# BEP21.net
KiCad netlist of a schematic drawn in EAGLE
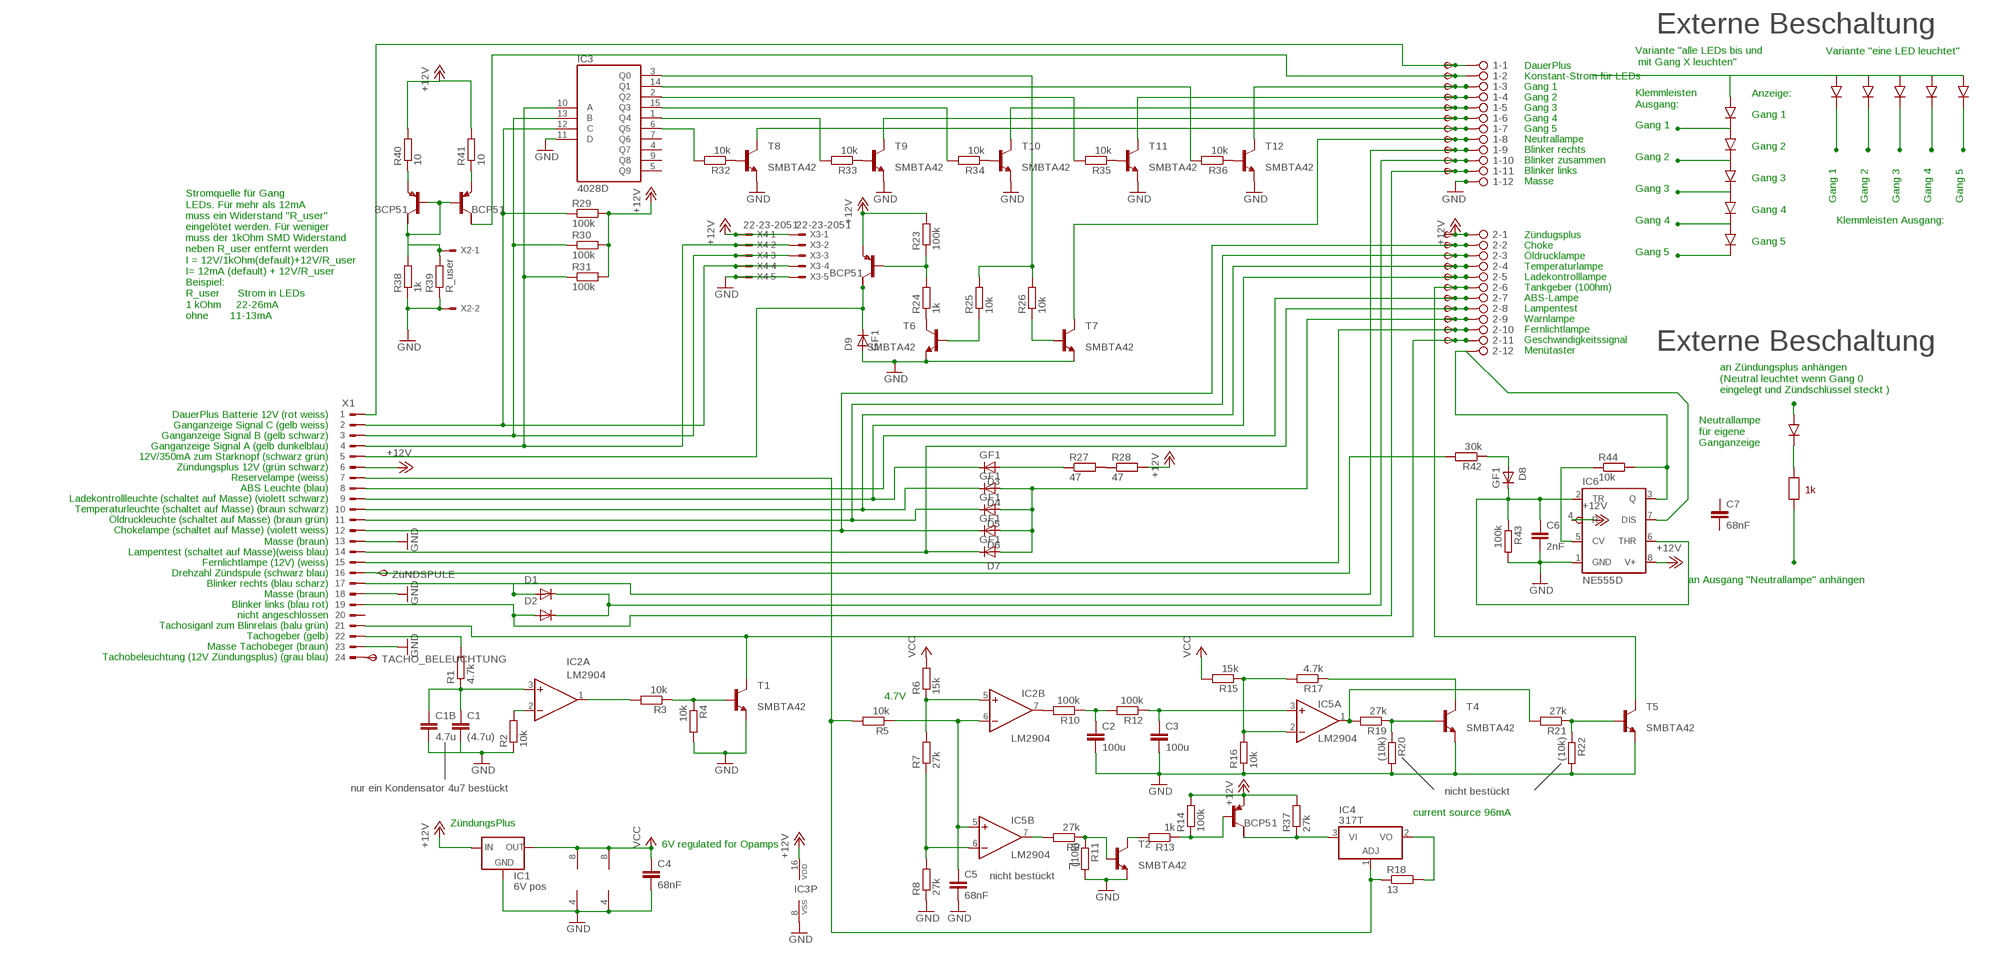
[diagram p0: schematic, sheet 1]

(export (version "E")
  (design (tool "Eeschema 10.0.6"))
  (components
    (comp (ref "1")
      (value "2081-1132")
      (footprint "eagle-import:12-PIN")
      (libsource (lib "eagle-import") (part "2081-1132"))
    )
    (comp (ref "2")
      (value "2081-1132")
      (footprint "eagle-import:12-PIN")
      (libsource (lib "eagle-import") (part "2081-1132"))
    )
    (comp (ref "C1")
      (value "(4.7u)")
      (footprint "eagle-import:C1206")
      (libsource (lib "eagle-import") (part "C-EUC1206"))
    )
    (comp (ref "C1B")
      (value "4.7u")
      (footprint "eagle-import:C0805K")
      (libsource (lib "eagle-import") (part "C-EUC0805K"))
    )
    (comp (ref "C2")
      (value "100u")
      (footprint "eagle-import:C1206K")
      (libsource (lib "eagle-import") (part "C-EUC1206K"))
    )
    (comp (ref "C3")
      (value "100u")
      (footprint "eagle-import:C1206K")
      (libsource (lib "eagle-import") (part "C-EUC1206K"))
    )
    (comp (ref "C4")
      (value "68nF")
      (footprint "eagle-import:C1206K")
      (libsource (lib "eagle-import") (part "C-EUC1206K"))
    )
    (comp (ref "C5")
      (value "68nF")
      (footprint "eagle-import:C1206K")
      (libsource (lib "eagle-import") (part "C-EUC1206K"))
    )
    (comp (ref "C6")
      (value "2nF")
      (footprint "eagle-import:C1206K")
      (libsource (lib "eagle-import") (part "C-EUC1206K"))
    )
    (comp (ref "C7")
      (value "68nF")
      (footprint "eagle-import:C1206K")
      (libsource (lib "eagle-import") (part "C-EUC1206K"))
    )
    (comp (ref "D1")
      (value "GF1")
      (footprint "eagle-import:SMA-DO214AC")
      (libsource (lib "eagle-import") (part "GF1"))
    )
    (comp (ref "D2")
      (value "GF1")
      (footprint "eagle-import:SMA-DO214AC")
      (libsource (lib "eagle-import") (part "GF1"))
    )
    (comp (ref "D3")
      (value "GF1")
      (footprint "eagle-import:SMA-DO214AC")
      (libsource (lib "eagle-import") (part "GF1"))
    )
    (comp (ref "D4")
      (value "GF1")
      (footprint "eagle-import:SMA-DO214AC")
      (libsource (lib "eagle-import") (part "GF1"))
    )
    (comp (ref "D5")
      (value "GF1")
      (footprint "eagle-import:SMA-DO214AC")
      (libsource (lib "eagle-import") (part "GF1"))
    )
    (comp (ref "D6")
      (value "GF1")
      (footprint "eagle-import:SMA-DO214AC")
      (libsource (lib "eagle-import") (part "GF1"))
    )
    (comp (ref "D7")
      (value "GF1")
      (footprint "eagle-import:SMA-DO214AC")
      (libsource (lib "eagle-import") (part "GF1"))
    )
    (comp (ref "D8")
      (value "GF1")
      (footprint "eagle-import:SMA-DO214AC")
      (libsource (lib "eagle-import") (part "GF1"))
    )
    (comp (ref "D9")
      (value "GF1")
      (footprint "eagle-import:SMA-DO214AC")
      (libsource (lib "eagle-import") (part "GF1"))
    )
    (comp (ref "IC1")
      (value "6V pos")
      (footprint "eagle-import:78LXX")
      (libsource (lib "eagle-import") (part "78LXX"))
    )
    (comp (ref "IC2")
      (value "LM2904")
      (footprint "eagle-import:SO08")
      (fields (field (name "IC") "LM2904"))
      (libsource (lib "eagle-import") (part "LM358D"))
    )
    (comp (ref "IC3")
      (value "4028D")
      (footprint "eagle-import:SO16")
      (libsource (lib "eagle-import") (part "4028D"))
    )
    (comp (ref "IC4")
      (value "317T")
      (footprint "eagle-import:TO220H")
      (libsource (lib "eagle-import") (part "317T"))
    )
    (comp (ref "IC5")
      (value "LM2904")
      (footprint "eagle-import:SO08")
      (libsource (lib "eagle-import") (part "linear_BMW_LM358D"))
    )
    (comp (ref "IC6")
      (value "NE555D")
      (footprint "eagle-import:SO08")
      (libsource (lib "eagle-import") (part "555DNE"))
    )
    (comp (ref "R1")
      (value "4.7k")
      (footprint "eagle-import:R0805")
      (libsource (lib "eagle-import") (part "R-EU_R0805"))
    )
    (comp (ref "R2")
      (value "10k")
      (footprint "eagle-import:R0805")
      (libsource (lib "eagle-import") (part "R-EU_R0805"))
    )
    (comp (ref "R3")
      (value "10k")
      (footprint "eagle-import:R0805")
      (libsource (lib "eagle-import") (part "R-EU_R0805"))
    )
    (comp (ref "R4")
      (value "10k")
      (footprint "eagle-import:R0805")
      (libsource (lib "eagle-import") (part "R-EU_R0805"))
    )
    (comp (ref "R5")
      (value "10k")
      (footprint "eagle-import:R0805")
      (libsource (lib "eagle-import") (part "R-EU_R0805"))
    )
    (comp (ref "R6")
      (value "15k")
      (footprint "eagle-import:R0805")
      (libsource (lib "eagle-import") (part "R-EU_R0805"))
    )
    (comp (ref "R7")
      (value "27k")
      (footprint "eagle-import:R0805")
      (libsource (lib "eagle-import") (part "R-EU_R0805"))
    )
    (comp (ref "R8")
      (value "27k")
      (footprint "eagle-import:R0805")
      (libsource (lib "eagle-import") (part "R-EU_R0805"))
    )
    (comp (ref "R9")
      (value "27k")
      (footprint "eagle-import:R0805")
      (libsource (lib "eagle-import") (part "R-EU_R0805"))
    )
    (comp (ref "R10")
      (value "100k")
      (footprint "eagle-import:R0805")
      (libsource (lib "eagle-import") (part "R-EU_R0805"))
    )
    (comp (ref "R11")
      (value "(10k)")
      (footprint "eagle-import:R0805")
      (libsource (lib "eagle-import") (part "R-EU_R0805"))
    )
    (comp (ref "R12")
      (value "100k")
      (footprint "eagle-import:R0805")
      (libsource (lib "eagle-import") (part "R-EU_R0805"))
    )
    (comp (ref "R13")
      (value "1k")
      (footprint "eagle-import:R0805")
      (libsource (lib "eagle-import") (part "R-EU_R0805"))
    )
    (comp (ref "R14")
      (value "100k")
      (footprint "eagle-import:R0805")
      (libsource (lib "eagle-import") (part "R-EU_R0805"))
    )
    (comp (ref "R15")
      (value "15k")
      (footprint "eagle-import:R0805")
      (libsource (lib "eagle-import") (part "R-EU_R0805"))
    )
    (comp (ref "R16")
      (value "10k")
      (footprint "eagle-import:R0805")
      (libsource (lib "eagle-import") (part "R-EU_R0805"))
    )
    (comp (ref "R17")
      (value "4.7k")
      (footprint "eagle-import:R0805")
      (libsource (lib "eagle-import") (part "R-EU_R0805"))
    )
    (comp (ref "R18")
      (value "13")
      (footprint "eagle-import:0207_10")
      (libsource (lib "eagle-import") (part "R-EU_0207/10"))
    )
    (comp (ref "R19")
      (value "27k")
      (footprint "eagle-import:R0805")
      (libsource (lib "eagle-import") (part "R-EU_R0805"))
    )
    (comp (ref "R20")
      (value "(10k)")
      (footprint "eagle-import:R0805")
      (libsource (lib "eagle-import") (part "R-EU_R0805"))
    )
    (comp (ref "R21")
      (value "27k")
      (footprint "eagle-import:R0805")
      (libsource (lib "eagle-import") (part "R-EU_R0805"))
    )
    (comp (ref "R22")
      (value "(10k)")
      (footprint "eagle-import:R0805")
      (libsource (lib "eagle-import") (part "R-EU_R0805"))
    )
    (comp (ref "R23")
      (value "100k")
      (footprint "eagle-import:R0805")
      (libsource (lib "eagle-import") (part "R-EU_R0805"))
    )
    (comp (ref "R24")
      (value "1k")
      (footprint "eagle-import:R0805")
      (libsource (lib "eagle-import") (part "R-EU_R0805"))
    )
    (comp (ref "R25")
      (value "10k")
      (footprint "eagle-import:R0805")
      (libsource (lib "eagle-import") (part "R-EU_R0805"))
    )
    (comp (ref "R26")
      (value "10k")
      (footprint "eagle-import:R0805")
      (libsource (lib "eagle-import") (part "R-EU_R0805"))
    )
    (comp (ref "R27")
      (value "47")
      (footprint "eagle-import:V235_17")
      (libsource (lib "eagle-import") (part "R-EU_V235/17"))
    )
    (comp (ref "R28")
      (value "47")
      (footprint "eagle-import:V235_17")
      (libsource (lib "eagle-import") (part "R-EU_V235/17"))
    )
    (comp (ref "R29")
      (value "100k")
      (footprint "eagle-import:R0805")
      (libsource (lib "eagle-import") (part "R-EU_R0805"))
    )
    (comp (ref "R30")
      (value "100k")
      (footprint "eagle-import:R0805")
      (libsource (lib "eagle-import") (part "R-EU_R0805"))
    )
    (comp (ref "R31")
      (value "100k")
      (footprint "eagle-import:R0805")
      (libsource (lib "eagle-import") (part "R-EU_R0805"))
    )
    (comp (ref "R32")
      (value "10k")
      (footprint "eagle-import:R0805")
      (libsource (lib "eagle-import") (part "R-EU_R0805"))
    )
    (comp (ref "R33")
      (value "10k")
      (footprint "eagle-import:R0805")
      (libsource (lib "eagle-import") (part "R-EU_R0805"))
    )
    (comp (ref "R34")
      (value "10k")
      (footprint "eagle-import:R0805")
      (libsource (lib "eagle-import") (part "R-EU_R0805"))
    )
    (comp (ref "R35")
      (value "10k")
      (footprint "eagle-import:R0805")
      (libsource (lib "eagle-import") (part "R-EU_R0805"))
    )
    (comp (ref "R36")
      (value "10k")
      (footprint "eagle-import:R0805")
      (libsource (lib "eagle-import") (part "R-EU_R0805"))
    )
    (comp (ref "R37")
      (value "27k")
      (footprint "eagle-import:R0805")
      (libsource (lib "eagle-import") (part "R-EU_R0805"))
    )
    (comp (ref "R38")
      (value "1k")
      (footprint "eagle-import:R0805")
      (libsource (lib "eagle-import") (part "R-EU_R0805"))
    )
    (comp (ref "R39")
      (value "R_user")
      (footprint "eagle-import:R0805")
      (libsource (lib "eagle-import") (part "R-EU_R0805"))
    )
    (comp (ref "R40")
      (value "10")
      (footprint "eagle-import:R0805")
      (libsource (lib "eagle-import") (part "R-EU_R0805"))
    )
    (comp (ref "R41")
      (value "10")
      (footprint "eagle-import:R0805")
      (libsource (lib "eagle-import") (part "R-EU_R0805"))
    )
    (comp (ref "R42")
      (value "30k")
      (footprint "eagle-import:R0805")
      (libsource (lib "eagle-import") (part "R-EU_R0805"))
    )
    (comp (ref "R43")
      (value "100k")
      (footprint "eagle-import:R0805")
      (libsource (lib "eagle-import") (part "R-EU_R0805"))
    )
    (comp (ref "R44")
      (value "10k")
      (footprint "eagle-import:R0805")
      (libsource (lib "eagle-import") (part "R-EU_R0805"))
    )
    (comp (ref "T")
      (value "BCP53T1")
      (footprint "eagle-import:SOT223")
      (fields (field (name "T") "BCP51"))
      (libsource (lib "eagle-import") (part "BCP53T1"))
    )
    (comp (ref "T1")
      (value "MMBTA42LT1-NPN-SOT23-BEC")
      (footprint "eagle-import:SOT23-BEC")
      (fields (field (name "T") "SMBTA42"))
      (libsource (lib "eagle-import") (part "-NPN-SOT23-BECMMBTA42LT1"))
    )
    (comp (ref "T2")
      (value "MMBTA42LT1-NPN-SOT23-BEC")
      (footprint "eagle-import:SOT23-BEC")
      (fields (field (name "T") "SMBTA42"))
      (libsource (lib "eagle-import") (part "-NPN-SOT23-BECMMBTA42LT1"))
    )
    (comp (ref "T3")
      (value "BCP53T1")
      (footprint "eagle-import:SOT223")
      (fields (field (name "T") "BCP51"))
      (libsource (lib "eagle-import") (part "BCP53T1"))
    )
    (comp (ref "T4")
      (value "MMBTA42LT1-NPN-SOT23-BEC")
      (footprint "eagle-import:SOT23-BEC")
      (fields (field (name "T") "SMBTA42"))
      (libsource (lib "eagle-import") (part "-NPN-SOT23-BECMMBTA42LT1"))
    )
    (comp (ref "T5")
      (value "MMBTA42LT1-NPN-SOT23-BEC")
      (footprint "eagle-import:SOT23-BEC")
      (fields (field (name "T") "SMBTA42"))
      (libsource (lib "eagle-import") (part "-NPN-SOT23-BECMMBTA42LT1"))
    )
    (comp (ref "T6")
      (value "MMBTA42LT1-NPN-SOT23-BEC")
      (footprint "eagle-import:SOT23-BEC")
      (fields (field (name "T") "SMBTA42"))
      (libsource (lib "eagle-import") (part "-NPN-SOT23-BECMMBTA42LT1"))
    )
    (comp (ref "T7")
      (value "MMBTA42LT1-NPN-SOT23-BEC")
      (footprint "eagle-import:SOT23-BEC")
      (fields (field (name "T") "SMBTA42"))
      (libsource (lib "eagle-import") (part "-NPN-SOT23-BECMMBTA42LT1"))
    )
    (comp (ref "T8")
      (value "MMBTA42LT1-NPN-SOT23-BEC")
      (footprint "eagle-import:SOT23-BEC")
      (fields (field (name "T") "SMBTA42"))
      (libsource (lib "eagle-import") (part "-NPN-SOT23-BECMMBTA42LT1"))
    )
    (comp (ref "T9")
      (value "MMBTA42LT1-NPN-SOT23-BEC")
      (footprint "eagle-import:SOT23-BEC")
      (fields (field (name "T") "SMBTA42"))
      (libsource (lib "eagle-import") (part "-NPN-SOT23-BECMMBTA42LT1"))
    )
    (comp (ref "T10")
      (value "MMBTA42LT1-NPN-SOT23-BEC")
      (footprint "eagle-import:SOT23-BEC")
      (fields (field (name "T") "SMBTA42"))
      (libsource (lib "eagle-import") (part "-NPN-SOT23-BECMMBTA42LT1"))
    )
    (comp (ref "T11")
      (value "MMBTA42LT1-NPN-SOT23-BEC")
      (footprint "eagle-import:SOT23-BEC")
      (fields (field (name "T") "SMBTA42"))
      (libsource (lib "eagle-import") (part "-NPN-SOT23-BECMMBTA42LT1"))
    )
    (comp (ref "T12")
      (value "MMBTA42LT1-NPN-SOT23-BEC")
      (footprint "eagle-import:SOT23-BEC")
      (fields (field (name "T") "SMBTA42"))
      (libsource (lib "eagle-import") (part "-NPN-SOT23-BECMMBTA42LT1"))
    )
    (comp (ref "T13")
      (value "BCP53T1")
      (footprint "eagle-import:SOT223")
      (fields (field (name "T") "BCP51"))
      (libsource (lib "eagle-import") (part "BCP53T1"))
    )
    (comp (ref "T14")
      (value "BCP53T1")
      (footprint "eagle-import:SOT223")
      (fields (field (name "T") "BCP51"))
      (libsource (lib "eagle-import") (part "BCP53T1"))
    )
    (comp (ref "TACHO_BELEUCHTUNG")
      (value "TPSP1_1MM")
      (footprint "eagle-import:P1_1.0MM")
      (libsource (lib "eagle-import") (part "TPSP1_1MM"))
    )
    (comp (ref "TP1")
      (value "TPSB1,27")
      (footprint "eagle-import:B1,27")
      (libsource (lib "eagle-import") (part "TPSB1,27"))
    )
    (comp (ref "TP2")
      (value "TPSB1,27")
      (footprint "eagle-import:B1,27")
      (libsource (lib "eagle-import") (part "TPSB1,27"))
    )
    (comp (ref "TP3")
      (value "TPSB1,27")
      (footprint "eagle-import:B1,27")
      (libsource (lib "eagle-import") (part "TPSB1,27"))
    )
    (comp (ref "TP4")
      (value "TPSB1,27")
      (footprint "eagle-import:B1,27")
      (libsource (lib "eagle-import") (part "TPSB1,27"))
    )
    (comp (ref "TP5")
      (value "TPSB1,27")
      (footprint "eagle-import:B1,27")
      (libsource (lib "eagle-import") (part "TPSB1,27"))
    )
    (comp (ref "TP6")
      (value "TPSB1,27")
      (footprint "eagle-import:B1,27")
      (libsource (lib "eagle-import") (part "TPSB1,27"))
    )
    (comp (ref "TP7")
      (value "TPSB1,27")
      (footprint "eagle-import:B1,27")
      (libsource (lib "eagle-import") (part "TPSB1,27"))
    )
    (comp (ref "TP8")
      (value "TPSB1,27")
      (footprint "eagle-import:B1,27")
      (libsource (lib "eagle-import") (part "TPSB1,27"))
    )
    (comp (ref "TP9")
      (value "TPSB1,27")
      (footprint "eagle-import:B1,27")
      (libsource (lib "eagle-import") (part "TPSB1,27"))
    )
    (comp (ref "TP10")
      (value "TPSB1,27")
      (footprint "eagle-import:B1,27")
      (libsource (lib "eagle-import") (part "TPSB1,27"))
    )
    (comp (ref "TP11")
      (value "TPSB1,27")
      (footprint "eagle-import:B1,27")
      (libsource (lib "eagle-import") (part "TPSB1,27"))
    )
    (comp (ref "TP12")
      (value "TPSB1,27")
      (footprint "eagle-import:B1,27")
      (libsource (lib "eagle-import") (part "TPSB1,27"))
    )
    (comp (ref "TP16")
      (value "TPSB1,27")
      (footprint "eagle-import:B1,27")
      (libsource (lib "eagle-import") (part "TPSB1,27"))
    )
    (comp (ref "TP17")
      (value "TPSB1,27")
      (footprint "eagle-import:B1,27")
      (libsource (lib "eagle-import") (part "TPSB1,27"))
    )
    (comp (ref "TP18")
      (value "TPSB1,27")
      (footprint "eagle-import:B1,27")
      (libsource (lib "eagle-import") (part "TPSB1,27"))
    )
    (comp (ref "TP19")
      (value "TPSB1,27")
      (footprint "eagle-import:B1,27")
      (libsource (lib "eagle-import") (part "TPSB1,27"))
    )
    (comp (ref "TP21")
      (value "TPSB1,27")
      (footprint "eagle-import:B1,27")
      (libsource (lib "eagle-import") (part "TPSB1,27"))
    )
    (comp (ref "TP22")
      (value "TPSB1,27")
      (footprint "eagle-import:B1,27")
      (libsource (lib "eagle-import") (part "TPSB1,27"))
    )
    (comp (ref "TP23")
      (value "TPSB1,27")
      (footprint "eagle-import:B1,27")
      (libsource (lib "eagle-import") (part "TPSB1,27"))
    )
    (comp (ref "TP24")
      (value "TPSB1,27")
      (footprint "eagle-import:B1,27")
      (libsource (lib "eagle-import") (part "TPSB1,27"))
    )
    (comp (ref "TP25")
      (value "TPSB1,27")
      (footprint "eagle-import:B1,27")
      (libsource (lib "eagle-import") (part "TPSB1,27"))
    )
    (comp (ref "TP26")
      (value "TPSB1,27")
      (footprint "eagle-import:B1,27")
      (libsource (lib "eagle-import") (part "TPSB1,27"))
    )
    (comp (ref "X1")
      (value "CON_BMW")
      (footprint "eagle-import:24-PIN")
      (libsource (lib "eagle-import") (part "CON_BMW"))
    )
    (comp (ref "X2")
      (value "22-23-2021")
      (footprint "eagle-import:22-23-2021")
      (fields (field (name "MF") "MOLEX"))
      (libsource (lib "eagle-import") (part "22-23-2021"))
    )
    (comp (ref "X3")
      (value "22-23-2051")
      (footprint "eagle-import:22-23-2051")
      (fields (field (name "MF") "MOLEX"))
      (libsource (lib "eagle-import") (part "22-23-2051"))
    )
    (comp (ref "X4")
      (value "22-23-2051")
      (footprint "eagle-import:22-23-2051")
      (fields (field (name "MF") "MOLEX"))
      (libsource (lib "eagle-import") (part "22-23-2051"))
    )
    (comp (ref "ZüNDSPULE")
      (value "TPSP1_1MM")
      (footprint "eagle-import:P1_1.0MM")
      (libsource (lib "eagle-import") (part "TPSP1_1MM"))
    )
  )
  (nets
    (net (code "1") (name "+12V") (class "Default")
      (node (ref "2") (pin "1") (pinfunction "KL_1") (pintype "passive"))
      (node (ref "IC1") (pin "IN") (pinfunction "IN_IN") (pintype "input"))
      (node (ref "IC3") (pin "16") (pinfunction "VDD_16") (pintype "power_in"))
      (node (ref "IC6") (pin "4") (pinfunction "R_4") (pintype "input"))
      (node (ref "IC6") (pin "8") (pinfunction "V+_8") (pintype "power_in"))
      (node (ref "R14") (pin "2") (pinfunction "2_2") (pintype "passive"))
      (node (ref "R23") (pin "2") (pinfunction "2_2") (pintype "passive"))
      (node (ref "R28") (pin "2") (pinfunction "2_2") (pintype "passive"))
      (node (ref "R29") (pin "2") (pinfunction "2_2") (pintype "passive"))
      (node (ref "R30") (pin "2") (pinfunction "2_2") (pintype "passive"))
      (node (ref "R31") (pin "2") (pinfunction "2_2") (pintype "passive"))
      (node (ref "R37") (pin "2") (pinfunction "2_2") (pintype "passive"))
      (node (ref "R40") (pin "2") (pinfunction "2_2") (pintype "passive"))
      (node (ref "R41") (pin "2") (pinfunction "2_2") (pintype "passive"))
      (node (ref "T") (pin "3") (pinfunction "E_3") (pintype "passive"))
      (node (ref "T3") (pin "3") (pinfunction "E_3") (pintype "passive"))
      (node (ref "TP12") (pin "TP") (pinfunction "PP_TP") (pintype "input"))
      (node (ref "X1") (pin "6") (pinfunction "6_6") (pintype "passive"))
      (node (ref "X3") (pin "1") (pinfunction "S_1") (pintype "passive"))
      (node (ref "X4") (pin "1") (pinfunction "S_1") (pintype "passive"))
    )
    (net (code "2") (name "GND") (class "Default")
      (node (ref "1") (pin "12") (pinfunction "KL_12") (pintype "passive"))
      (node (ref "C1") (pin "2") (pinfunction "2_2") (pintype "passive"))
      (node (ref "C1B") (pin "2") (pinfunction "2_2") (pintype "passive"))
      (node (ref "C2") (pin "2") (pinfunction "2_2") (pintype "passive"))
      (node (ref "C3") (pin "2") (pinfunction "2_2") (pintype "passive"))
      (node (ref "C4") (pin "2") (pinfunction "2_2") (pintype "passive"))
      (node (ref "C5") (pin "2") (pinfunction "2_2") (pintype "passive"))
      (node (ref "C6") (pin "2") (pinfunction "2_2") (pintype "passive"))
      (node (ref "D9") (pin "A") (pinfunction "A_A") (pintype "passive"))
      (node (ref "IC1") (pin "GND") (pinfunction "GND_GND") (pintype "input"))
      (node (ref "IC2") (pin "4") (pinfunction "V-_4") (pintype "power_in"))
      (node (ref "IC3") (pin "11") (pinfunction "D_11") (pintype "input"))
      (node (ref "IC3") (pin "8") (pinfunction "VSS_8") (pintype "power_in"))
      (node (ref "IC5") (pin "4") (pinfunction "V-_4") (pintype "power_in"))
      (node (ref "IC6") (pin "1") (pinfunction "GND_1") (pintype "power_in"))
      (node (ref "R11") (pin "2") (pinfunction "2_2") (pintype "passive"))
      (node (ref "R16") (pin "1") (pinfunction "1_1") (pintype "passive"))
      (node (ref "R2") (pin "1") (pinfunction "1_1") (pintype "passive"))
      (node (ref "R20") (pin "2") (pinfunction "2_2") (pintype "passive"))
      (node (ref "R22") (pin "2") (pinfunction "2_2") (pintype "passive"))
      (node (ref "R38") (pin "1") (pinfunction "1_1") (pintype "passive"))
      (node (ref "R39") (pin "1") (pinfunction "1_1") (pintype "passive"))
      (node (ref "R4") (pin "2") (pinfunction "2_2") (pintype "passive"))
      (node (ref "R43") (pin "2") (pinfunction "2_2") (pintype "passive"))
      (node (ref "R8") (pin "1") (pinfunction "1_1") (pintype "passive"))
      (node (ref "T1") (pin "E") (pinfunction "E_E") (pintype "passive"))
      (node (ref "T10") (pin "E") (pinfunction "E_E") (pintype "passive"))
      (node (ref "T11") (pin "E") (pinfunction "E_E") (pintype "passive"))
      (node (ref "T12") (pin "E") (pinfunction "E_E") (pintype "passive"))
      (node (ref "T2") (pin "E") (pinfunction "E_E") (pintype "passive"))
      (node (ref "T4") (pin "E") (pinfunction "E_E") (pintype "passive"))
      (node (ref "T5") (pin "E") (pinfunction "E_E") (pintype "passive"))
      (node (ref "T6") (pin "E") (pinfunction "E_E") (pintype "passive"))
      (node (ref "T7") (pin "E") (pinfunction "E_E") (pintype "passive"))
      (node (ref "T8") (pin "E") (pinfunction "E_E") (pintype "passive"))
      (node (ref "T9") (pin "E") (pinfunction "E_E") (pintype "passive"))
      (node (ref "X1") (pin "13") (pinfunction "13_13") (pintype "passive"))
      (node (ref "X1") (pin "18") (pinfunction "18_18") (pintype "passive"))
      (node (ref "X1") (pin "23") (pinfunction "23_23") (pintype "passive"))
      (node (ref "X2") (pin "2") (pinfunction "S_2") (pintype "passive"))
      (node (ref "X3") (pin "5") (pinfunction "S_5") (pintype "passive"))
      (node (ref "X4") (pin "5") (pinfunction "S_5") (pintype "passive"))
    )
    (net (code "3") (name "Net-(1A-KL)") (class "Default")
      (node (ref "1") (pin "1") (pinfunction "KL_1") (pintype "passive"))
      (node (ref "TP1") (pin "TP") (pinfunction "PP_TP") (pintype "input"))
      (node (ref "X1") (pin "1") (pinfunction "1_1") (pintype "passive"))
    )
    (net (code "4") (name "Net-(1B-KL)") (class "Default")
      (node (ref "1") (pin "10") (pinfunction "KL_10") (pintype "passive"))
      (node (ref "D1") (pin "K") (pinfunction "C_K") (pintype "passive"))
      (node (ref "D2") (pin "K") (pinfunction "C_K") (pintype "passive"))
      (node (ref "TP10") (pin "TP") (pinfunction "PP_TP") (pintype "input"))
    )
    (net (code "5") (name "Net-(1C-KL)") (class "Default")
      (node (ref "1") (pin "11") (pinfunction "KL_11") (pintype "passive"))
      (node (ref "D2") (pin "A") (pinfunction "A_A") (pintype "passive"))
      (node (ref "TP11") (pin "TP") (pinfunction "PP_TP") (pintype "input"))
      (node (ref "X1") (pin "19") (pinfunction "19_19") (pintype "passive"))
    )
    (net (code "6") (name "Net-(1E-KL)") (class "Default")
      (node (ref "1") (pin "2") (pinfunction "KL_2") (pintype "passive"))
      (node (ref "T14") (pin "2") (pinfunction "C_2") (pintype "passive"))
      (node (ref "TP2") (pin "TP") (pinfunction "PP_TP") (pintype "input"))
    )
    (net (code "7") (name "Net-(1F-KL)") (class "Default")
      (node (ref "1") (pin "3") (pinfunction "KL_3") (pintype "passive"))
      (node (ref "T12") (pin "C") (pinfunction "C_C") (pintype "passive"))
      (node (ref "TP3") (pin "TP") (pinfunction "PP_TP") (pintype "input"))
    )
    (net (code "8") (name "Net-(1G-KL)") (class "Default")
      (node (ref "1") (pin "4") (pinfunction "KL_4") (pintype "passive"))
      (node (ref "T11") (pin "C") (pinfunction "C_C") (pintype "passive"))
      (node (ref "TP4") (pin "TP") (pinfunction "PP_TP") (pintype "input"))
    )
    (net (code "9") (name "Net-(1H-KL)") (class "Default")
      (node (ref "1") (pin "5") (pinfunction "KL_5") (pintype "passive"))
      (node (ref "T10") (pin "C") (pinfunction "C_C") (pintype "passive"))
      (node (ref "TP5") (pin "TP") (pinfunction "PP_TP") (pintype "input"))
    )
    (net (code "10") (name "Net-(1I-KL)") (class "Default")
      (node (ref "1") (pin "6") (pinfunction "KL_6") (pintype "passive"))
      (node (ref "T9") (pin "C") (pinfunction "C_C") (pintype "passive"))
      (node (ref "TP6") (pin "TP") (pinfunction "PP_TP") (pintype "input"))
    )
    (net (code "11") (name "Net-(1J-KL)") (class "Default")
      (node (ref "1") (pin "7") (pinfunction "KL_7") (pintype "passive"))
      (node (ref "T8") (pin "C") (pinfunction "C_C") (pintype "passive"))
      (node (ref "TP7") (pin "TP") (pinfunction "PP_TP") (pintype "input"))
    )
    (net (code "12") (name "Net-(1K-KL)") (class "Default")
      (node (ref "1") (pin "8") (pinfunction "KL_8") (pintype "passive"))
      (node (ref "T7") (pin "C") (pinfunction "C_C") (pintype "passive"))
      (node (ref "TP8") (pin "TP") (pinfunction "PP_TP") (pintype "input"))
    )
    (net (code "13") (name "Net-(1L-KL)") (class "Default")
      (node (ref "1") (pin "9") (pinfunction "KL_9") (pintype "passive"))
      (node (ref "D1") (pin "A") (pinfunction "A_A") (pintype "passive"))
      (node (ref "TP9") (pin "TP") (pinfunction "PP_TP") (pintype "input"))
      (node (ref "X1") (pin "17") (pinfunction "17_17") (pintype "passive"))
    )
    (net (code "14") (name "Net-(2B-KL)") (class "Default")
      (node (ref "2") (pin "10") (pinfunction "KL_10") (pintype "passive"))
      (node (ref "TP25") (pin "TP") (pinfunction "PP_TP") (pintype "input"))
      (node (ref "X1") (pin "15") (pinfunction "15_15") (pintype "passive"))
    )
    (net (code "15") (name "Net-(2C-KL)") (class "Default")
      (node (ref "2") (pin "11") (pinfunction "KL_11") (pintype "passive"))
      (node (ref "T1") (pin "C") (pinfunction "C_C") (pintype "passive"))
      (node (ref "TP26") (pin "TP") (pinfunction "PP_TP") (pintype "input"))
      (node (ref "X1") (pin "21") (pinfunction "21_21") (pintype "passive"))
    )
    (net (code "16") (name "Net-(2D-KL)") (class "Default")
      (node (ref "2") (pin "12") (pinfunction "KL_12") (pintype "passive"))
      (node (ref "IC6") (pin "3") (pinfunction "Q_3") (pintype "output"))
      (node (ref "IC6") (pin "7") (pinfunction "DIS_7") (pintype "input"))
      (node (ref "R44") (pin "2") (pinfunction "2_2") (pintype "passive"))
    )
    (net (code "17") (name "Net-(2E-KL)") (class "Default")
      (node (ref "2") (pin "2") (pinfunction "KL_2") (pintype "passive"))
      (node (ref "D6") (pin "K") (pinfunction "C_K") (pintype "passive"))
      (node (ref "TP16") (pin "TP") (pinfunction "PP_TP") (pintype "input"))
      (node (ref "X1") (pin "12") (pinfunction "12_12") (pintype "passive"))
    )
    (net (code "18") (name "Net-(2F-KL)") (class "Default")
      (node (ref "2") (pin "3") (pinfunction "KL_3") (pintype "passive"))
      (node (ref "D5") (pin "K") (pinfunction "C_K") (pintype "passive"))
      (node (ref "TP17") (pin "TP") (pinfunction "PP_TP") (pintype "input"))
      (node (ref "X1") (pin "11") (pinfunction "11_11") (pintype "passive"))
    )
    (net (code "19") (name "Net-(2G-KL)") (class "Default")
      (node (ref "2") (pin "4") (pinfunction "KL_4") (pintype "passive"))
      (node (ref "D4") (pin "K") (pinfunction "C_K") (pintype "passive"))
      (node (ref "TP18") (pin "TP") (pinfunction "PP_TP") (pintype "input"))
      (node (ref "X1") (pin "10") (pinfunction "10_10") (pintype "passive"))
    )
    (net (code "20") (name "Net-(2H-KL)") (class "Default")
      (node (ref "2") (pin "5") (pinfunction "KL_5") (pintype "passive"))
      (node (ref "D3") (pin "K") (pinfunction "C_K") (pintype "passive"))
      (node (ref "TP19") (pin "TP") (pinfunction "PP_TP") (pintype "input"))
      (node (ref "X1") (pin "9") (pinfunction "9_9") (pintype "passive"))
    )
    (net (code "21") (name "Net-(2I-KL)") (class "Default")
      (node (ref "2") (pin "6") (pinfunction "KL_6") (pintype "passive"))
      (node (ref "T5") (pin "C") (pinfunction "C_C") (pintype "passive"))
      (node (ref "TP21") (pin "TP") (pinfunction "PP_TP") (pintype "input"))
    )
    (net (code "22") (name "Net-(2J-KL)") (class "Default")
      (node (ref "2") (pin "7") (pinfunction "KL_7") (pintype "passive"))
      (node (ref "TP22") (pin "TP") (pinfunction "PP_TP") (pintype "input"))
      (node (ref "X1") (pin "8") (pinfunction "8_8") (pintype "passive"))
    )
    (net (code "23") (name "Net-(2K-KL)") (class "Default")
      (node (ref "2") (pin "8") (pinfunction "KL_8") (pintype "passive"))
      (node (ref "D7") (pin "K") (pinfunction "C_K") (pintype "passive"))
      (node (ref "TP23") (pin "TP") (pinfunction "PP_TP") (pintype "input"))
      (node (ref "X1") (pin "14") (pinfunction "14_14") (pintype "passive"))
    )
    (net (code "24") (name "Net-(2L-KL)") (class "Default")
      (node (ref "2") (pin "9") (pinfunction "KL_9") (pintype "passive"))
      (node (ref "D4") (pin "A") (pinfunction "A_A") (pintype "passive"))
      (node (ref "D5") (pin "A") (pinfunction "A_A") (pintype "passive"))
      (node (ref "D6") (pin "A") (pinfunction "A_A") (pintype "passive"))
      (node (ref "D7") (pin "A") (pinfunction "A_A") (pintype "passive"))
      (node (ref "TP24") (pin "TP") (pinfunction "PP_TP") (pintype "input"))
    )
    (net (code "25") (name "Net-(C2-Pad1)") (class "Default")
      (node (ref "C2") (pin "1") (pinfunction "1_1") (pintype "passive"))
      (node (ref "R10") (pin "1") (pinfunction "1_1") (pintype "passive"))
      (node (ref "R12") (pin "2") (pinfunction "2_2") (pintype "passive"))
    )
    (net (code "26") (name "Net-(D3-PadA)") (class "Default")
      (node (ref "D3") (pin "A") (pinfunction "A_A") (pintype "passive"))
      (node (ref "R27") (pin "1") (pinfunction "1_1") (pintype "passive"))
    )
    (net (code "27") (name "Net-(D8-C)") (class "Default")
      (node (ref "C6") (pin "1") (pinfunction "1_1") (pintype "passive"))
      (node (ref "D8") (pin "K") (pinfunction "C_K") (pintype "passive"))
      (node (ref "IC6") (pin "2") (pinfunction "TR_2") (pintype "input"))
      (node (ref "IC6") (pin "6") (pinfunction "THR_6") (pintype "input"))
      (node (ref "R43") (pin "1") (pinfunction "1_1") (pintype "passive"))
    )
    (net (code "28") (name "Net-(D8-PadA)") (class "Default")
      (node (ref "D8") (pin "A") (pinfunction "A_A") (pintype "passive"))
      (node (ref "R42") (pin "1") (pinfunction "1_1") (pintype "passive"))
    )
    (net (code "29") (name "Net-(D9-C)") (class "Default")
      (node (ref "D9") (pin "K") (pinfunction "C_K") (pintype "passive"))
      (node (ref "T") (pin "2") (pinfunction "C_2") (pintype "passive"))
      (node (ref "X1") (pin "5") (pinfunction "5_5") (pintype "passive"))
    )
    (net (code "30") (name "Net-(IC2A-+IN)") (class "Default")
      (node (ref "C1") (pin "1") (pinfunction "1_1") (pintype "passive"))
      (node (ref "C1B") (pin "1") (pinfunction "1_1") (pintype "passive"))
      (node (ref "IC2") (pin "3") (pinfunction "+IN_3") (pintype "input"))
      (node (ref "R1") (pin "1") (pinfunction "1_1") (pintype "passive"))
    )
    (net (code "31") (name "Net-(IC2A--IN)") (class "Default")
      (node (ref "IC2") (pin "2") (pinfunction "-IN_2") (pintype "input"))
      (node (ref "R2") (pin "2") (pinfunction "2_2") (pintype "passive"))
    )
    (net (code "32") (name "Net-(IC2A-OUT)") (class "Default")
      (node (ref "IC2") (pin "1") (pinfunction "OUT_1") (pintype "output"))
      (node (ref "R3") (pin "2") (pinfunction "2_2") (pintype "passive"))
    )
    (net (code "33") (name "Net-(IC2B-+IN)") (class "Default")
      (node (ref "IC2") (pin "5") (pinfunction "+IN_5") (pintype "input"))
      (node (ref "R6") (pin "1") (pinfunction "1_1") (pintype "passive"))
      (node (ref "R7") (pin "2") (pinfunction "2_2") (pintype "passive"))
    )
    (net (code "34") (name "Net-(IC2B--IN)") (class "Default")
      (node (ref "C5") (pin "1") (pinfunction "1_1") (pintype "passive"))
      (node (ref "IC2") (pin "6") (pinfunction "-IN_6") (pintype "input"))
      (node (ref "IC5") (pin "5") (pinfunction "+IN_5") (pintype "input"))
      (node (ref "R5") (pin "1") (pinfunction "1_1") (pintype "passive"))
    )
    (net (code "35") (name "Net-(IC2B-OUT)") (class "Default")
      (node (ref "IC2") (pin "7") (pinfunction "OUT_7") (pintype "output"))
      (node (ref "R10") (pin "2") (pinfunction "2_2") (pintype "passive"))
    )
    (net (code "36") (name "Net-(IC3A-A)") (class "Default")
      (node (ref "IC3") (pin "10") (pinfunction "A_10") (pintype "input"))
      (node (ref "R31") (pin "1") (pinfunction "1_1") (pintype "passive"))
      (node (ref "X1") (pin "4") (pinfunction "4_4") (pintype "passive"))
      (node (ref "X3") (pin "2") (pinfunction "S_2") (pintype "passive"))
      (node (ref "X4") (pin "2") (pinfunction "S_2") (pintype "passive"))
    )
    (net (code "37") (name "Net-(IC3A-B)") (class "Default")
      (node (ref "IC3") (pin "13") (pinfunction "B_13") (pintype "input"))
      (node (ref "R30") (pin "1") (pinfunction "1_1") (pintype "passive"))
      (node (ref "X1") (pin "3") (pinfunction "3_3") (pintype "passive"))
      (node (ref "X3") (pin "3") (pinfunction "S_3") (pintype "passive"))
      (node (ref "X4") (pin "3") (pinfunction "S_3") (pintype "passive"))
    )
    (net (code "38") (name "Net-(IC3A-C)") (class "Default")
      (node (ref "IC3") (pin "12") (pinfunction "C_12") (pintype "input"))
      (node (ref "R29") (pin "1") (pinfunction "1_1") (pintype "passive"))
      (node (ref "X1") (pin "2") (pinfunction "2_2") (pintype "passive"))
      (node (ref "X3") (pin "4") (pinfunction "S_4") (pintype "passive"))
      (node (ref "X4") (pin "4") (pinfunction "S_4") (pintype "passive"))
    )
    (net (code "39") (name "Net-(IC3A-Q0)") (class "Default")
      (node (ref "IC3") (pin "3") (pinfunction "Q0_3") (pintype "output"))
      (node (ref "R25") (pin "2") (pinfunction "2_2") (pintype "passive"))
      (node (ref "R26") (pin "2") (pinfunction "2_2") (pintype "passive"))
    )
    (net (code "40") (name "Net-(IC3A-Q1)") (class "Default")
      (node (ref "IC3") (pin "14") (pinfunction "Q1_14") (pintype "output"))
      (node (ref "R36") (pin "2") (pinfunction "2_2") (pintype "passive"))
    )
    (net (code "41") (name "Net-(IC3A-Q2)") (class "Default")
      (node (ref "IC3") (pin "2") (pinfunction "Q2_2") (pintype "output"))
      (node (ref "R35") (pin "2") (pinfunction "2_2") (pintype "passive"))
    )
    (net (code "42") (name "Net-(IC3A-Q3)") (class "Default")
      (node (ref "IC3") (pin "15") (pinfunction "Q3_15") (pintype "output"))
      (node (ref "R34") (pin "2") (pinfunction "2_2") (pintype "passive"))
    )
    (net (code "43") (name "Net-(IC3A-Q4)") (class "Default")
      (node (ref "IC3") (pin "1") (pinfunction "Q4_1") (pintype "output"))
      (node (ref "R33") (pin "2") (pinfunction "2_2") (pintype "passive"))
    )
    (net (code "44") (name "Net-(IC3A-Q5)") (class "Default")
      (node (ref "IC3") (pin "6") (pinfunction "Q5_6") (pintype "output"))
      (node (ref "R32") (pin "2") (pinfunction "2_2") (pintype "passive"))
    )
    (net (code "45") (name "Net-(IC4-ADJ)") (class "Default")
      (node (ref "IC4") (pin "1") (pinfunction "ADJ_1") (pintype "input"))
      (node (ref "R18") (pin "1") (pinfunction "1_1") (pintype "passive"))
      (node (ref "R5") (pin "2") (pinfunction "2_2") (pintype "passive"))
      (node (ref "X1") (pin "7") (pinfunction "7_7") (pintype "passive"))
    )
    (net (code "46") (name "Net-(IC4-VI)") (class "Default")
      (node (ref "IC4") (pin "3") (pinfunction "VI_3") (pintype "input"))
      (node (ref "R37") (pin "1") (pinfunction "1_1") (pintype "passive"))
      (node (ref "T3") (pin "2") (pinfunction "C_2") (pintype "passive"))
    )
    (net (code "47") (name "Net-(IC4-VO)") (class "Default")
      (node (ref "IC4") (pin "2") (pinfunction "VO_2") (pintype "passive"))
      (node (ref "R18") (pin "2") (pinfunction "2_2") (pintype "passive"))
    )
    (net (code "48") (name "Net-(IC5A-+IN)") (class "Default")
      (node (ref "C3") (pin "1") (pinfunction "1_1") (pintype "passive"))
      (node (ref "IC5") (pin "3") (pinfunction "+IN_3") (pintype "input"))
      (node (ref "R12") (pin "1") (pinfunction "1_1") (pintype "passive"))
    )
    (net (code "49") (name "Net-(IC5A--IN)") (class "Default")
      (node (ref "IC5") (pin "2") (pinfunction "-IN_2") (pintype "input"))
      (node (ref "R15") (pin "1") (pinfunction "1_1") (pintype "passive"))
      (node (ref "R16") (pin "2") (pinfunction "2_2") (pintype "passive"))
      (node (ref "R17") (pin "2") (pinfunction "2_2") (pintype "passive"))
    )
    (net (code "50") (name "Net-(IC5A-OUT)") (class "Default")
      (node (ref "IC5") (pin "1") (pinfunction "OUT_1") (pintype "output"))
      (node (ref "R19") (pin "2") (pinfunction "2_2") (pintype "passive"))
      (node (ref "R21") (pin "2") (pinfunction "2_2") (pintype "passive"))
    )
    (net (code "51") (name "Net-(IC5B--IN)") (class "Default")
      (node (ref "IC5") (pin "6") (pinfunction "-IN_6") (pintype "input"))
      (node (ref "R7") (pin "1") (pinfunction "1_1") (pintype "passive"))
      (node (ref "R8") (pin "2") (pinfunction "2_2") (pintype "passive"))
    )
    (net (code "52") (name "Net-(IC5B-OUT)") (class "Default")
      (node (ref "IC5") (pin "7") (pinfunction "OUT_7") (pintype "output"))
      (node (ref "R9") (pin "2") (pinfunction "2_2") (pintype "passive"))
    )
    (net (code "53") (name "Net-(IC6-CV)") (class "Default")
      (node (ref "IC6") (pin "5") (pinfunction "CV_5") (pintype "input"))
      (node (ref "R44") (pin "1") (pinfunction "1_1") (pintype "passive"))
    )
    (net (code "54") (name "Net-(R1-Pad2)") (class "Default")
      (node (ref "R1") (pin "2") (pinfunction "2_2") (pintype "passive"))
      (node (ref "X1") (pin "22") (pinfunction "22_22") (pintype "passive"))
    )
    (net (code "55") (name "Net-(R3-Pad1)") (class "Default")
      (node (ref "R3") (pin "1") (pinfunction "1_1") (pintype "passive"))
      (node (ref "R4") (pin "1") (pinfunction "1_1") (pintype "passive"))
      (node (ref "T1") (pin "B") (pinfunction "B_B") (pintype "passive"))
    )
    (net (code "56") (name "Net-(R11-Pad1)") (class "Default")
      (node (ref "R11") (pin "1") (pinfunction "1_1") (pintype "passive"))
      (node (ref "R9") (pin "1") (pinfunction "1_1") (pintype "passive"))
      (node (ref "T2") (pin "B") (pinfunction "B_B") (pintype "passive"))
    )
    (net (code "57") (name "Net-(R13-Pad2)") (class "Default")
      (node (ref "R13") (pin "2") (pinfunction "2_2") (pintype "passive"))
      (node (ref "T2") (pin "C") (pinfunction "C_C") (pintype "passive"))
    )
    (net (code "58") (name "Net-(R17-Pad1)") (class "Default")
      (node (ref "R17") (pin "1") (pinfunction "1_1") (pintype "passive"))
      (node (ref "T4") (pin "C") (pinfunction "C_C") (pintype "passive"))
    )
    (net (code "59") (name "Net-(R19-Pad1)") (class "Default")
      (node (ref "R19") (pin "1") (pinfunction "1_1") (pintype "passive"))
      (node (ref "R20") (pin "1") (pinfunction "1_1") (pintype "passive"))
      (node (ref "T4") (pin "B") (pinfunction "B_B") (pintype "passive"))
    )
    (net (code "60") (name "Net-(R21-Pad1)") (class "Default")
      (node (ref "R21") (pin "1") (pinfunction "1_1") (pintype "passive"))
      (node (ref "R22") (pin "1") (pinfunction "1_1") (pintype "passive"))
      (node (ref "T5") (pin "B") (pinfunction "B_B") (pintype "passive"))
    )
    (net (code "61") (name "Net-(R24-Pad1)") (class "Default")
      (node (ref "R24") (pin "1") (pinfunction "1_1") (pintype "passive"))
      (node (ref "T6") (pin "C") (pinfunction "C_C") (pintype "passive"))
    )
    (net (code "62") (name "Net-(R25-Pad1)") (class "Default")
      (node (ref "R25") (pin "1") (pinfunction "1_1") (pintype "passive"))
      (node (ref "T6") (pin "B") (pinfunction "B_B") (pintype "passive"))
    )
    (net (code "63") (name "Net-(R26-Pad1)") (class "Default")
      (node (ref "R26") (pin "1") (pinfunction "1_1") (pintype "passive"))
      (node (ref "T7") (pin "B") (pinfunction "B_B") (pintype "passive"))
    )
    (net (code "64") (name "Net-(R27-Pad2)") (class "Default")
      (node (ref "R27") (pin "2") (pinfunction "2_2") (pintype "passive"))
      (node (ref "R28") (pin "1") (pinfunction "1_1") (pintype "passive"))
    )
    (net (code "65") (name "Net-(R32-Pad1)") (class "Default")
      (node (ref "R32") (pin "1") (pinfunction "1_1") (pintype "passive"))
      (node (ref "T8") (pin "B") (pinfunction "B_B") (pintype "passive"))
    )
    (net (code "66") (name "Net-(R33-Pad1)") (class "Default")
      (node (ref "R33") (pin "1") (pinfunction "1_1") (pintype "passive"))
      (node (ref "T9") (pin "B") (pinfunction "B_B") (pintype "passive"))
    )
    (net (code "67") (name "Net-(R34-Pad1)") (class "Default")
      (node (ref "R34") (pin "1") (pinfunction "1_1") (pintype "passive"))
      (node (ref "T10") (pin "B") (pinfunction "B_B") (pintype "passive"))
    )
    (net (code "68") (name "Net-(R35-Pad1)") (class "Default")
      (node (ref "R35") (pin "1") (pinfunction "1_1") (pintype "passive"))
      (node (ref "T11") (pin "B") (pinfunction "B_B") (pintype "passive"))
    )
    (net (code "69") (name "Net-(R36-Pad1)") (class "Default")
      (node (ref "R36") (pin "1") (pinfunction "1_1") (pintype "passive"))
      (node (ref "T12") (pin "B") (pinfunction "B_B") (pintype "passive"))
    )
    (net (code "70") (name "Net-(T-B)") (class "Default")
      (node (ref "R23") (pin "1") (pinfunction "1_1") (pintype "passive"))
      (node (ref "R24") (pin "2") (pinfunction "2_2") (pintype "passive"))
      (node (ref "T") (pin "1") (pinfunction "B_1") (pintype "passive"))
    )
    (net (code "71") (name "Net-(T3-B)") (class "Default")
      (node (ref "R13") (pin "1") (pinfunction "1_1") (pintype "passive"))
      (node (ref "R14") (pin "1") (pinfunction "1_1") (pintype "passive"))
      (node (ref "T3") (pin "1") (pinfunction "B_1") (pintype "passive"))
    )
    (net (code "72") (name "Net-(T13-B)") (class "Default")
      (node (ref "R38") (pin "2") (pinfunction "2_2") (pintype "passive"))
      (node (ref "R39") (pin "2") (pinfunction "2_2") (pintype "passive"))
      (node (ref "T13") (pin "1") (pinfunction "B_1") (pintype "passive"))
      (node (ref "T13") (pin "2") (pinfunction "C_2") (pintype "passive"))
      (node (ref "T14") (pin "1") (pinfunction "B_1") (pintype "passive"))
      (node (ref "X2") (pin "1") (pinfunction "S_1") (pintype "passive"))
    )
    (net (code "73") (name "Net-(T13-E)") (class "Default")
      (node (ref "R40") (pin "1") (pinfunction "1_1") (pintype "passive"))
      (node (ref "T13") (pin "3") (pinfunction "E_3") (pintype "passive"))
    )
    (net (code "74") (name "Net-(T14-E)") (class "Default")
      (node (ref "R41") (pin "1") (pinfunction "1_1") (pintype "passive"))
      (node (ref "T14") (pin "3") (pinfunction "E_3") (pintype "passive"))
    )
    (net (code "75") (name "Net-(TACHO_BELEUCHTUNG-PP)") (class "Default")
      (node (ref "TACHO_BELEUCHTUNG") (pin "TP") (pinfunction "PP_TP") (pintype "input"))
      (node (ref "X1") (pin "24") (pinfunction "24_24") (pintype "passive"))
    )
    (net (code "76") (name "Net-(ZüNDSPULE-PP)") (class "Default")
      (node (ref "R42") (pin "2") (pinfunction "2_2") (pintype "passive"))
      (node (ref "X1") (pin "16") (pinfunction "16_16") (pintype "passive"))
      (node (ref "ZüNDSPULE") (pin "TP") (pinfunction "PP_TP") (pintype "input"))
    )
    (net (code "77") (name "VCC") (class "Default")
      (node (ref "C4") (pin "1") (pinfunction "1_1") (pintype "passive"))
      (node (ref "IC1") (pin "OUT") (pinfunction "OUT_OUT") (pintype "passive"))
      (node (ref "IC2") (pin "8") (pinfunction "V+_8") (pintype "power_in"))
      (node (ref "IC5") (pin "8") (pinfunction "V+_8") (pintype "power_in"))
      (node (ref "R15") (pin "2") (pinfunction "2_2") (pintype "passive"))
      (node (ref "R6") (pin "2") (pinfunction "2_2") (pintype "passive"))
    )
    (net (code "78") (name "unconnected-(C7-Pad1)") (class "Default")
      (node (ref "C7") (pin "1") (pinfunction "1_1") (pintype "passive"))
    )
    (net (code "79") (name "unconnected-(C7-Pad2)") (class "Default")
      (node (ref "C7") (pin "2") (pinfunction "2_2") (pintype "passive"))
    )
    (net (code "80") (name "unconnected-(IC3A-Q6-Pad7)") (class "Default")
      (node (ref "IC3") (pin "7") (pinfunction "Q6_7") (pintype "output"))
    )
    (net (code "81") (name "unconnected-(IC3A-Q7-Pad4)") (class "Default")
      (node (ref "IC3") (pin "4") (pinfunction "Q7_4") (pintype "output"))
    )
    (net (code "82") (name "unconnected-(IC3A-Q8-Pad9)") (class "Default")
      (node (ref "IC3") (pin "9") (pinfunction "Q8_9") (pintype "output"))
    )
    (net (code "83") (name "unconnected-(IC3A-Q9-Pad5)") (class "Default")
      (node (ref "IC3") (pin "5") (pinfunction "Q9_5") (pintype "output"))
    )
    (net (code "84") (name "unconnected-(T-C{slash}-Pad4)") (class "Default")
      (node (ref "T") (pin "4") (pinfunction "C/_4") (pintype "passive"))
    )
    (net (code "85") (name "unconnected-(T3-C{slash}-Pad4)") (class "Default")
      (node (ref "T3") (pin "4") (pinfunction "C/_4") (pintype "passive"))
    )
    (net (code "86") (name "unconnected-(T13-C{slash}-Pad4)") (class "Default")
      (node (ref "T13") (pin "4") (pinfunction "C/_4") (pintype "passive"))
    )
    (net (code "87") (name "unconnected-(T14-C{slash}-Pad4)") (class "Default")
      (node (ref "T14") (pin "4") (pinfunction "C/_4") (pintype "passive"))
    )
    (net (code "88") (name "unconnected-(X1-Pad20)") (class "Default")
      (node (ref "X1") (pin "20") (pinfunction "20_20") (pintype "passive"))
    )
  )
)
